# SDP21_Daughter_Board_Schematic.net
KiCad netlist of a schematic drawn in Altium Designer
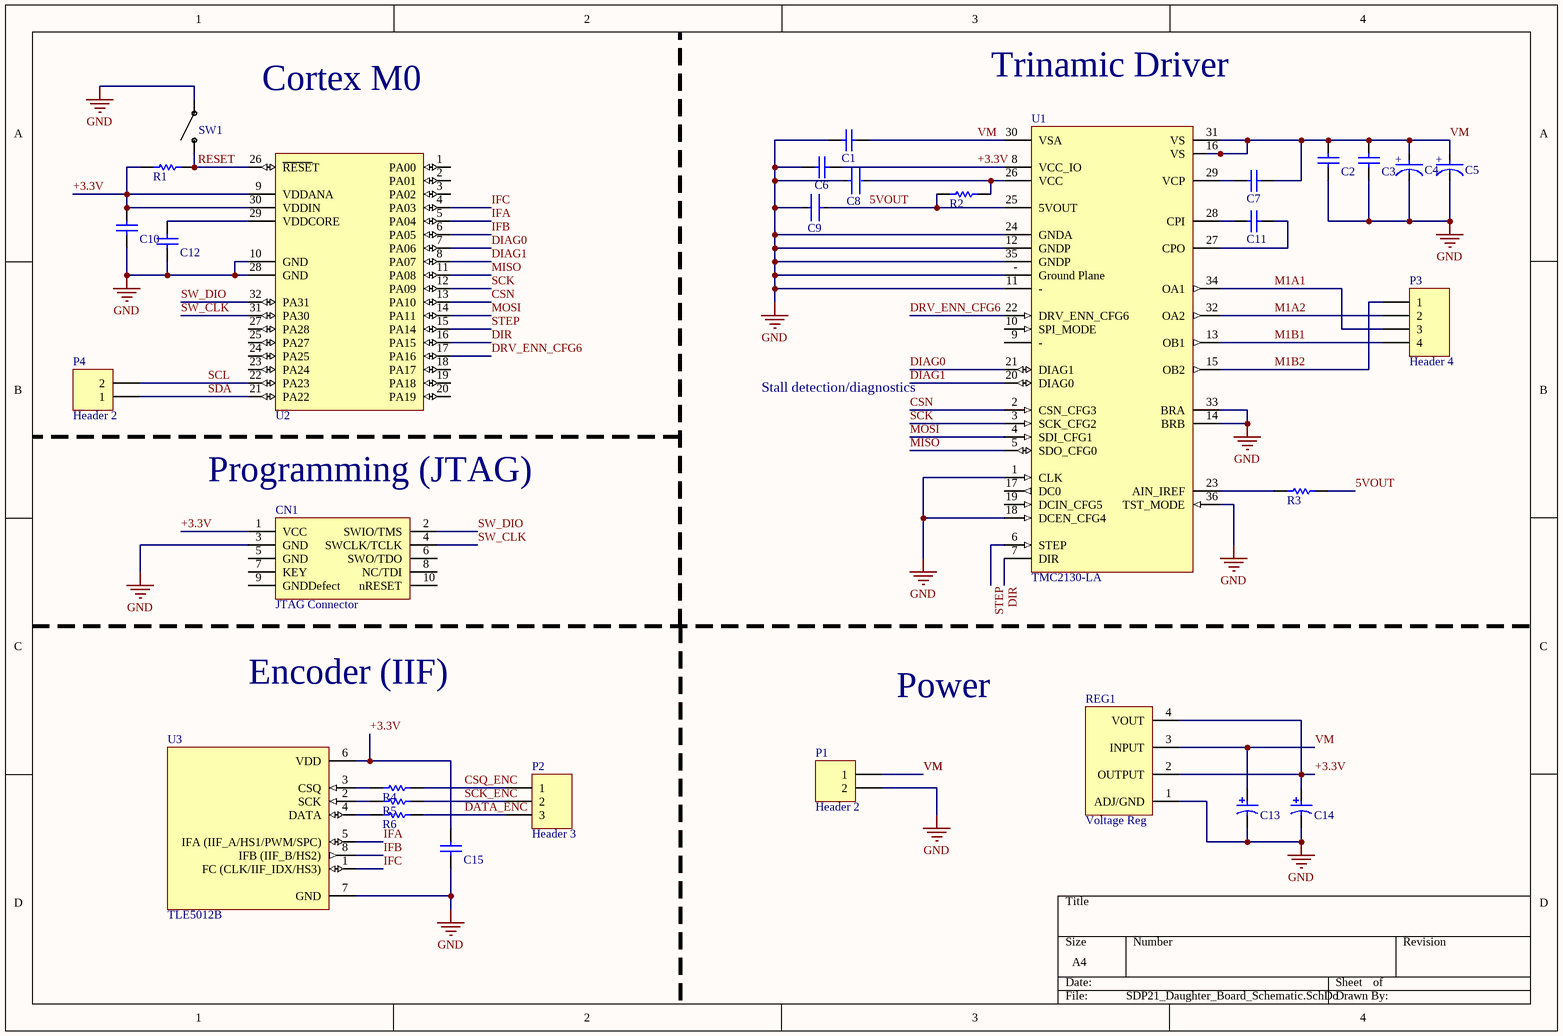
[diagram p0: SDP21_Daughter_Board_Schematic.SchDoc]

(export (version "E")
  (design (tool "Eeschema 10.0.6"))
  (components
    (comp (ref "C1")
      (value "CGA3E2X7R1H104K080AA")
      (footprint "CAPC1608X90X20LL10")
      (description "Chip Capacitor, 0.1 uF, +/- 10%, 50 V, -55 to 125 degC, 0603 (1608 Metric), RoHS, Tape and Reel")
      (fields (field (name "VOLTAGE") "50V") (field (name "TOLERANCE") "10%"))
      (libsource (lib "Altium Content Vault") (part "CAP-NP-2"))
    )
    (comp (ref "C2")
      (value "CGA3E2X7R1H104K080AA")
      (footprint "CAPC1608X90X20LL10")
      (description "Chip Capacitor, 0.1 uF, +/- 10%, 50 V, -55 to 125 degC, 0603 (1608 Metric), RoHS, Tape and Reel")
      (fields (field (name "VOLTAGE") "50V") (field (name "TOLERANCE") "10%"))
      (libsource (lib "Altium Content Vault") (part "CAP-NP-2"))
    )
    (comp (ref "C3")
      (value "C1210C476M4PACTU")
      (footprint "CAPC3225X270X50LL20T25")
      (description "Chip Capacitor, 47 uF, +/- 20%, 16 V, -55 to 85 degC, 1210 (3225 Metric), RoHS, Tape and Reel")
      (fields (field (name "TOLERANCE") "±20%") (field (name "MANUFACTURER") "Kemet"))
      (libsource (lib "Altium Content Vault") (part "CAP-NP-2"))
    )
    (comp (ref "C4")
      (value "EEE-FK1H101P")
      (footprint "FP-EEE-FK1H101P-MFG")
      (description "CAP ALUM 100UF 20% 50V SMD")
      (fields
        (field (name "TOLERANCE") "20%")
        (field (name "OCTOPART") "https://octopart.com/eeefk1h101p-panasonic-4642841")
      )
      (libsource (lib "Altium Content Vault") (part "cf48714ba7e38822c1575c7ec0b6d1f"))
    )
    (comp (ref "C5")
      (value "EEE-FK1H101P")
      (footprint "FP-EEE-FK1H101P-MFG")
      (description "CAP ALUM 100UF 20% 50V SMD")
      (fields
        (field (name "TOLERANCE") "20%")
        (field (name "OCTOPART") "https://octopart.com/eeefk1h101p-panasonic-4642841")
      )
      (libsource (lib "Altium Content Vault") (part "cf48714ba7e38822c1575c7ec0b6d1f"))
    )
    (comp (ref "C6")
      (value "CGA3E2X7R1H104K080AA")
      (footprint "CAPC1608X90X20LL10")
      (description "Chip Capacitor, 0.1 uF, +/- 10%, 50 V, -55 to 125 degC, 0603 (1608 Metric), RoHS, Tape and Reel")
      (fields (field (name "VOLTAGE") "50V") (field (name "TOLERANCE") "10%"))
      (libsource (lib "Altium Content Vault") (part "CAP-NP-2"))
    )
    (comp (ref "C7")
      (value "CGA3E2X7R1H104K080AA")
      (footprint "CAPC1608X90X20LL10")
      (description "Chip Capacitor, 0.1 uF, +/- 10%, 50 V, -55 to 125 degC, 0603 (1608 Metric), RoHS, Tape and Reel")
      (fields (field (name "VOLTAGE") "50V") (field (name "TOLERANCE") "10%"))
      (libsource (lib "Altium Content Vault") (part "CAP-NP-2"))
    )
    (comp (ref "C8")
      (value "C0603C474K4RACTU")
      (footprint "FP-C0603C-CF-MFG")
      (description "CAP CER 0.47UF 16V X7R 0603")
      (fields
        (field (name "TOLERANCE") "0.1")
        (field (name "OCTOPART") "https://octopart.com/c0603c474k4ractu-kemet-109683")
      )
      (libsource (lib "Altium Content Vault") (part "b4654b650e69147ec39a6b967a45e02"))
    )
    (comp (ref "C9")
      (value "C0603C475K9PACTU")
      (footprint "FP-C0603-CG-MFG")
      (description "CAP CER 4.7UF 6.3V X5R 0603")
      (fields (field (name "TOLERANCE") "10%") (field (name "MANUFACTURER") "Kemet"))
      (libsource (lib "Altium Content Vault") (part "11868f565c42a9108669ba33697ecf6"))
    )
    (comp (ref "C10")
      (value "GRM188R60J106ME47D")
      (footprint "CAPC1608X90X35NL10T15")
      (fields (field (name "MANUFACTURER") "Murata"))
      (libsource (lib "Altium Content Vault") (part "CAP"))
    )
    (comp (ref "C11")
      (value "CC0603KRX7R9BB223")
      (footprint "CAPC1608X90X40ML10T20")
      (description "Chip Capacitor, 22 nF, +/- 10%, 50 V, -55 to 125 degC, 0603 (1608 Metric), RoHS, Tape and Reel")
      (fields (field (name "MANUFACTURER") "Yageo") (field (name "TOLERANCE") "10%"))
      (libsource (lib "Altium Content Vault") (part "CAP-NP-2"))
    )
    (comp (ref "C12")
      (value "GRM188R60J106ME47D")
      (footprint "CAPC1608X90X35NL10T15")
      (fields (field (name "MANUFACTURER") "Murata"))
      (libsource (lib "Altium Content Vault") (part "CAP"))
    )
    (comp (ref "C13")
      (value "T491A106K010AT")
      (footprint "KEMT-A-3216-18-2_M")
      (description "Capacitor, Tantalum, 10 uF, +/- 10%, 10 V, -55 to 125 degC, 2-Pin SMD (1206), RoHS, Tape and Reel")
      (fields (field (name "TOLERANCE") "±10%") (field (name "MANUFACTURER") "Kemet"))
      (libsource (lib "Altium Content Vault") (part "CAP-P-2"))
    )
    (comp (ref "C14")
      (value "TAJA226K010RNJ")
      (footprint "AVX-TAJ-A-2_L")
      (description "Chip Capacitor, 22 uF, +/- 10%, 10 V, -55 to 125 degC, 1206 (3216 Metric), RoHS, Tape and Reel")
      (fields (field (name "MANUFACTURER") "AVX") (field (name "TOLERANCE") "10%"))
      (libsource (lib "Altium Content Vault") (part "CAP-P-2"))
    )
    (comp (ref "C15")
      (value "CGA3E2X7R1H104K080AA")
      (footprint "CAPC1608X90X20LL10")
      (description "Chip Capacitor, 0.1 uF, +/- 10%, 50 V, -55 to 125 degC, 0603 (1608 Metric), RoHS, Tape and Reel")
      (fields (field (name "VOLTAGE") "50V") (field (name "TOLERANCE") "10%"))
      (libsource (lib "Altium Content Vault") (part "CAP-NP-2"))
    )
    (comp (ref "CN1")
      (value "JTAG Connector")
      (footprint "Header 5x2 - 50mil")
      (libsource (lib "SDP21_Symbols") (part "JTAG Connector"))
    )
    (comp (ref "P1")
      (value "Header 2")
      (footprint "HDR1X2")
      (description "Header, 2-Pin")
      (fields (field (name "PUBLISHER") "Altium Limited"))
      (libsource (lib "Miscellaneous Connectors") (part "Header 2"))
    )
    (comp (ref "P2")
      (value "Header 3")
      (footprint "HDR1X3")
      (description "Header, 3-Pin")
      (fields (field (name "PUBLISHER") "Altium Limited"))
      (libsource (lib "Miscellaneous Connectors") (part "Header 3"))
    )
    (comp (ref "P3")
      (value "Header 4")
      (footprint "HDR1X4")
      (description "Header, 4-Pin")
      (fields (field (name "PUBLISHER") "Altium Limited"))
      (libsource (lib "Miscellaneous Connectors") (part "Header 4"))
    )
    (comp (ref "P4")
      (value "Header 2")
      (footprint "HDR1X2")
      (description "Header, 2-Pin")
      (fields (field (name "PUBLISHER") "Altium Limited"))
      (libsource (lib "") (part "Header 2_1"))
    )
    (comp (ref "R1")
      (value "ERJ3EKF1002V")
      (footprint "RESC1609X55X30LL15T15")
      (description "Chip Resistor, 10 KOhm, +/- 1%, 0.1 W, -55 to 155 degC, 0603 (1608 Metric), RoHS, Tape and Reel")
      (fields (field (name "TOLERANCE") "1%") (field (name "MANUFACTURER") "Panasonic"))
      (libsource (lib "Altium Content Vault") (part "RES-2"))
    )
    (comp (ref "R2")
      (value "CRCW06033R30JNEA")
      (footprint "RESC1609X50X30ML10T20")
      (fields (field (name "MANUFACTURER") "Vishay Dale"))
      (libsource (lib "Altium Content Vault") (part "RES"))
    )
    (comp (ref "R3")
      (value "ERJ3EKF1002V")
      (footprint "RESC1609X55X30LL15T15")
      (description "Chip Resistor, 10 KOhm, +/- 1%, 0.1 W, -55 to 155 degC, 0603 (1608 Metric), RoHS, Tape and Reel")
      (fields (field (name "TOLERANCE") "1%") (field (name "MANUFACTURER") "Panasonic"))
      (libsource (lib "Altium Content Vault") (part "RES-2"))
    )
    (comp (ref "R4")
      (value "470R 1% 0603(1608)")
      (footprint "RESC0603(1608)_M")
      (description "470R 0.1W 1% 0603 (1608 Metric)  SMD")
      (fields (field (name "POWER") "0.1 W") (field (name "TOLERANCE") "1 %"))
      (libsource (lib "Altium Content Vault") (part "RES"))
    )
    (comp (ref "R5")
      (value "470R 1% 0603(1608)")
      (footprint "RESC0603(1608)_M")
      (description "470R 0.1W 1% 0603 (1608 Metric)  SMD")
      (fields (field (name "POWER") "0.1 W") (field (name "TOLERANCE") "1 %"))
      (libsource (lib "Altium Content Vault") (part "RES"))
    )
    (comp (ref "R6")
      (value "470R 1% 0603(1608)")
      (footprint "RESC0603(1608)_M")
      (description "470R 0.1W 1% 0603 (1608 Metric)  SMD")
      (fields (field (name "POWER") "0.1 W") (field (name "TOLERANCE") "1 %"))
      (libsource (lib "Altium Content Vault") (part "RES"))
    )
    (comp (ref "REG1")
      (value "Voltage Reg")
      (footprint "SOT223")
      (libsource (lib "SDP21_Symbols") (part "Voltage Reg"))
    )
    (comp (ref "SW1")
      (value "PTS525SM15SMTR2 LFS")
      (footprint "PTS525 SM08 SMTR2 LFS")
      (description "SWITCH TACTILE SPST-NO 0.02A 15V")
      (libsource (lib "SDP21_Symbols") (part "Tactile Push Button"))
    )
    (comp (ref "U1")
      (value "TMC2130-LA")
      (footprint "QFN-36")
      (description "TMC2130-LA Trinamic Driver QFN-36")
      (libsource (lib "SDP21_Symbols") (part "TMC2130-LA"))
    )
    (comp (ref "U2")
      (value "ATSAMD21E15B-AUT")
      (footprint "TQFP-32")
      (description "IC MCU 32BIT 32KB FLASH 32TQFP")
      (libsource (lib "SDP21_Symbols") (part "ATSAMD21E15B-AUT"))
    )
    (comp (ref "U3")
      (value "TLE5012B")
      (footprint "PG-DSO-8")
      (description "TLE5012B GMR-Based Angle Sensor PG-DSO-8")
      (libsource (lib "SDP21_Symbols") (part "TLE5012B"))
    )
  )
  (nets
    (net (code "1") (name "/+3.3V") (class "Default")
      (node (ref "C10") (pin "2") (pinfunction "2_2") (pintype "passive"))
      (node (ref "C14") (pin "1") (pinfunction "1_1") (pintype "passive"))
      (node (ref "C15") (pin "2") (pinfunction "2_2") (pintype "passive"))
      (node (ref "C6") (pin "2") (pinfunction "2_2") (pintype "passive"))
      (node (ref "CN1") (pin "1") (pinfunction "VCC_1") (pintype "power_in"))
      (node (ref "R1") (pin "1") (pinfunction "1_1") (pintype "passive"))
      (node (ref "REG1") (pin "2") (pinfunction "OUTPUT_2") (pintype "passive"))
      (node (ref "REG1") (pin "4") (pinfunction "VOUT_4") (pintype "passive"))
      (node (ref "U1") (pin "8") (pinfunction "VCC_IO_8") (pintype "power_in"))
      (node (ref "U2") (pin "30") (pinfunction "VDDIN_30") (pintype "power_in"))
      (node (ref "U2") (pin "9") (pinfunction "VDDANA_9") (pintype "power_in"))
      (node (ref "U3") (pin "6") (pinfunction "VDD_6") (pintype "power_in"))
    )
    (net (code "2") (name "/5VOUT") (class "Default")
      (node (ref "C9") (pin "1") (pinfunction "1_1") (pintype "passive"))
      (node (ref "R2") (pin "1") (pinfunction "1_1") (pintype "passive"))
      (node (ref "R3") (pin "2") (pinfunction "2_2") (pintype "passive"))
      (node (ref "U1") (pin "25") (pinfunction "5VOUT_25") (pintype "power_in"))
    )
    (net (code "3") (name "/CSN") (class "Default")
      (node (ref "U1") (pin "2") (pinfunction "CSN_CFG3_2") (pintype "input"))
      (node (ref "U2") (pin "13") (pinfunction "PA10_13") (pintype "bidirectional"))
    )
    (net (code "4") (name "/CSQ_ENC") (class "Default")
      (node (ref "P2") (pin "1") (pinfunction "1_1") (pintype "passive"))
      (node (ref "R4") (pin "2") (pinfunction "2_2") (pintype "passive"))
    )
    (net (code "5") (name "/DATA_ENC") (class "Default")
      (node (ref "P2") (pin "3") (pinfunction "3_3") (pintype "passive"))
      (node (ref "R6") (pin "2") (pinfunction "2_2") (pintype "passive"))
    )
    (net (code "6") (name "/DIAG0") (class "Default")
      (node (ref "U1") (pin "21") (pinfunction "DIAG1_21") (pintype "bidirectional"))
      (node (ref "U2") (pin "7") (pinfunction "PA06_7") (pintype "bidirectional"))
    )
    (net (code "7") (name "/DIAG1") (class "Default")
      (node (ref "U1") (pin "20") (pinfunction "DIAG0_20") (pintype "bidirectional"))
      (node (ref "U2") (pin "8") (pinfunction "PA07_8") (pintype "bidirectional"))
    )
    (net (code "8") (name "/DIR") (class "Default")
      (node (ref "U1") (pin "7") (pinfunction "DIR_7") (pintype "passive"))
      (node (ref "U2") (pin "16") (pinfunction "PA15_16") (pintype "bidirectional"))
    )
    (net (code "9") (name "/DRV_ENN_CFG6") (class "Default")
      (node (ref "U1") (pin "22") (pinfunction "DRV_ENN_CFG6_22") (pintype "input"))
      (node (ref "U2") (pin "17") (pinfunction "PA16_17") (pintype "bidirectional"))
    )
    (net (code "10") (name "/IFA") (class "Default")
      (node (ref "U2") (pin "5") (pinfunction "PA04_5") (pintype "bidirectional"))
      (node (ref "U3") (pin "5") (pinfunction "IFA_(IIF_A/HS1/PWM/SPC)_5") (pintype "bidirectional"))
    )
    (net (code "11") (name "/IFB") (class "Default")
      (node (ref "U2") (pin "6") (pinfunction "PA05_6") (pintype "bidirectional"))
      (node (ref "U3") (pin "8") (pinfunction "IFB_(IIF_B/HS2)_8") (pintype "output"))
    )
    (net (code "12") (name "/IFC") (class "Default")
      (node (ref "U2") (pin "4") (pinfunction "PA03_4") (pintype "bidirectional"))
      (node (ref "U3") (pin "1") (pinfunction "FC_(CLK/IIF_IDX/HS3)_1") (pintype "bidirectional"))
    )
    (net (code "13") (name "/M1A1") (class "Default")
      (node (ref "P3") (pin "3") (pinfunction "3_3") (pintype "passive"))
      (node (ref "U1") (pin "34") (pinfunction "OA1_34") (pintype "output"))
    )
    (net (code "14") (name "/M1A2") (class "Default")
      (node (ref "P3") (pin "2") (pinfunction "2_2") (pintype "passive"))
      (node (ref "U1") (pin "32") (pinfunction "OA2_32") (pintype "output"))
    )
    (net (code "15") (name "/M1B1") (class "Default")
      (node (ref "P3") (pin "4") (pinfunction "4_4") (pintype "passive"))
      (node (ref "U1") (pin "13") (pinfunction "OB1_13") (pintype "output"))
    )
    (net (code "16") (name "/M1B2") (class "Default")
      (node (ref "P3") (pin "1") (pinfunction "1_1") (pintype "passive"))
      (node (ref "U1") (pin "15") (pinfunction "OB2_15") (pintype "output"))
    )
    (net (code "17") (name "/MISO") (class "Default")
      (node (ref "U1") (pin "5") (pinfunction "SDO_CFG0_5") (pintype "bidirectional"))
      (node (ref "U2") (pin "11") (pinfunction "PA08_11") (pintype "bidirectional"))
    )
    (net (code "18") (name "/MOSI") (class "Default")
      (node (ref "U1") (pin "4") (pinfunction "SDI_CFG1_4") (pintype "input"))
      (node (ref "U2") (pin "14") (pinfunction "PA11_14") (pintype "bidirectional"))
    )
    (net (code "19") (name "/RESET") (class "Default")
      (node (ref "R1") (pin "2") (pinfunction "2_2") (pintype "passive"))
      (node (ref "SW1") (pin "1") (pinfunction "1_1") (pintype "passive"))
      (node (ref "U2") (pin "26") (pinfunction "~{RESE}T_26") (pintype "bidirectional"))
    )
    (net (code "20") (name "/SCK") (class "Default")
      (node (ref "U1") (pin "3") (pinfunction "SCK_CFG2_3") (pintype "input"))
      (node (ref "U2") (pin "12") (pinfunction "PA09_12") (pintype "bidirectional"))
    )
    (net (code "21") (name "/SCK_ENC") (class "Default")
      (node (ref "P2") (pin "2") (pinfunction "2_2") (pintype "passive"))
      (node (ref "R5") (pin "2") (pinfunction "2_2") (pintype "passive"))
    )
    (net (code "22") (name "/SCL") (class "Default")
      (node (ref "P4") (pin "2") (pinfunction "2_2") (pintype "passive"))
      (node (ref "U2") (pin "22") (pinfunction "PA23_22") (pintype "bidirectional"))
    )
    (net (code "23") (name "/SDA") (class "Default")
      (node (ref "P4") (pin "1") (pinfunction "1_1") (pintype "passive"))
      (node (ref "U2") (pin "21") (pinfunction "PA22_21") (pintype "bidirectional"))
    )
    (net (code "24") (name "/STEP") (class "Default")
      (node (ref "U1") (pin "6") (pinfunction "STEP_6") (pintype "input"))
      (node (ref "U2") (pin "15") (pinfunction "PA14_15") (pintype "bidirectional"))
    )
    (net (code "25") (name "/SW_CLK") (class "Default")
      (node (ref "CN1") (pin "4") (pinfunction "SWCLK/TCLK_4") (pintype "power_in"))
      (node (ref "U2") (pin "31") (pinfunction "PA30_31") (pintype "bidirectional"))
    )
    (net (code "26") (name "/SW_DIO") (class "Default")
      (node (ref "CN1") (pin "2") (pinfunction "SWIO/TMS_2") (pintype "power_in"))
      (node (ref "U2") (pin "32") (pinfunction "PA31_32") (pintype "bidirectional"))
    )
    (net (code "27") (name "/VM") (class "Default")
      (node (ref "C1") (pin "2") (pinfunction "2_2") (pintype "passive"))
      (node (ref "C13") (pin "1") (pinfunction "1_1") (pintype "passive"))
      (node (ref "C2") (pin "2") (pinfunction "2_2") (pintype "passive"))
      (node (ref "C3") (pin "2") (pinfunction "2_2") (pintype "passive"))
      (node (ref "C4") (pin "2") (pinfunction "A_2") (pintype "passive"))
      (node (ref "C5") (pin "2") (pinfunction "A_2") (pintype "passive"))
      (node (ref "C7") (pin "1") (pinfunction "1_1") (pintype "passive"))
      (node (ref "P1") (pin "1") (pinfunction "1_1") (pintype "passive"))
      (node (ref "REG1") (pin "3") (pinfunction "INPUT_3") (pintype "passive"))
      (node (ref "U1") (pin "16") (pinfunction "VS_16") (pintype "power_in"))
      (node (ref "U1") (pin "30") (pinfunction "VSA_30") (pintype "power_in"))
      (node (ref "U1") (pin "31") (pinfunction "VS_31") (pintype "power_in"))
    )
    (net (code "28") (name "GND") (class "Default")
      (node (ref "C1") (pin "1") (pinfunction "1_1") (pintype "passive"))
      (node (ref "C10") (pin "1") (pinfunction "1_1") (pintype "passive"))
      (node (ref "C12") (pin "1") (pinfunction "1_1") (pintype "passive"))
      (node (ref "C13") (pin "2") (pinfunction "2_2") (pintype "passive"))
      (node (ref "C14") (pin "2") (pinfunction "2_2") (pintype "passive"))
      (node (ref "C15") (pin "1") (pinfunction "1_1") (pintype "passive"))
      (node (ref "C2") (pin "1") (pinfunction "1_1") (pintype "passive"))
      (node (ref "C3") (pin "1") (pinfunction "1_1") (pintype "passive"))
      (node (ref "C4") (pin "1") (pinfunction "C_1") (pintype "passive"))
      (node (ref "C5") (pin "1") (pinfunction "C_1") (pintype "passive"))
      (node (ref "C6") (pin "1") (pinfunction "1_1") (pintype "passive"))
      (node (ref "C8") (pin "1") (pinfunction "1_1") (pintype "passive"))
      (node (ref "C9") (pin "2") (pinfunction "2_2") (pintype "passive"))
      (node (ref "CN1") (pin "3") (pinfunction "GND_3") (pintype "power_in"))
      (node (ref "P1") (pin "2") (pinfunction "2_2") (pintype "passive"))
      (node (ref "REG1") (pin "1") (pinfunction "ADJ/GND_1") (pintype "passive"))
      (node (ref "SW1") (pin "2") (pinfunction "2_2") (pintype "passive"))
      (node (ref "U1") (pin "-") (pinfunction "Ground_Plane_-") (pintype "passive"))
      (node (ref "U1") (pin "1") (pinfunction "CLK_1") (pintype "input"))
      (node (ref "U1") (pin "11") (pinfunction "-_11") (pintype "passive"))
      (node (ref "U1") (pin "12") (pinfunction "GNDP_12") (pintype "power_in"))
      (node (ref "U1") (pin "14") (pinfunction "BRB_14") (pintype "passive"))
      (node (ref "U1") (pin "18") (pinfunction "DCEN_CFG4_18") (pintype "input"))
      (node (ref "U1") (pin "24") (pinfunction "GNDA_24") (pintype "power_in"))
      (node (ref "U1") (pin "33") (pinfunction "BRA_33") (pintype "passive"))
      (node (ref "U1") (pin "35") (pinfunction "GNDP_35") (pintype "power_in"))
      (node (ref "U1") (pin "36") (pinfunction "TST_MODE_36") (pintype "input"))
      (node (ref "U2") (pin "10") (pinfunction "GND_10") (pintype "power_in"))
      (node (ref "U2") (pin "28") (pinfunction "GND_28") (pintype "power_in"))
      (node (ref "U3") (pin "7") (pinfunction "GND_7") (pintype "power_in"))
    )
    (net (code "29") (name "Net-(U1-AIN_IREF)") (class "Default")
      (node (ref "R3") (pin "1") (pinfunction "1_1") (pintype "passive"))
      (node (ref "U1") (pin "23") (pinfunction "AIN_IREF_23") (pintype "passive"))
    )
    (net (code "30") (name "Net-(U1-CPI)") (class "Default")
      (node (ref "C11") (pin "1") (pinfunction "1_1") (pintype "passive"))
      (node (ref "U1") (pin "28") (pinfunction "CPI_28") (pintype "passive"))
    )
    (net (code "31") (name "Net-(U1-CPO)") (class "Default")
      (node (ref "C11") (pin "2") (pinfunction "2_2") (pintype "passive"))
      (node (ref "U1") (pin "27") (pinfunction "CPO_27") (pintype "passive"))
    )
    (net (code "32") (name "Net-(U1-VCC)") (class "Default")
      (node (ref "C8") (pin "2") (pinfunction "2_2") (pintype "passive"))
      (node (ref "R2") (pin "2") (pinfunction "2_2") (pintype "passive"))
      (node (ref "U1") (pin "26") (pinfunction "VCC_26") (pintype "power_in"))
    )
    (net (code "33") (name "Net-(U1-VCP)") (class "Default")
      (node (ref "C7") (pin "2") (pinfunction "2_2") (pintype "passive"))
      (node (ref "U1") (pin "29") (pinfunction "VCP_29") (pintype "passive"))
    )
    (net (code "34") (name "Net-(U2-VDDCORE)") (class "Default")
      (node (ref "C12") (pin "2") (pinfunction "2_2") (pintype "passive"))
      (node (ref "U2") (pin "29") (pinfunction "VDDCORE_29") (pintype "power_in"))
    )
    (net (code "35") (name "Net-(U3-CSQ)") (class "Default")
      (node (ref "R4") (pin "1") (pinfunction "1_1") (pintype "passive"))
      (node (ref "U3") (pin "3") (pinfunction "CSQ_3") (pintype "input"))
    )
    (net (code "36") (name "Net-(U3-DATA)") (class "Default")
      (node (ref "R6") (pin "1") (pinfunction "1_1") (pintype "passive"))
      (node (ref "U3") (pin "4") (pinfunction "DATA_4") (pintype "bidirectional"))
    )
    (net (code "37") (name "Net-(U3-SCK)") (class "Default")
      (node (ref "R5") (pin "1") (pinfunction "1_1") (pintype "passive"))
      (node (ref "U3") (pin "2") (pinfunction "SCK_2") (pintype "input"))
    )
    (net (code "38") (name "unconnected-(CN1-GND-Pad5)") (class "Default")
      (node (ref "CN1") (pin "5") (pinfunction "GND_5") (pintype "power_in"))
    )
    (net (code "39") (name "unconnected-(CN1-GNDDefect-Pad9)") (class "Default")
      (node (ref "CN1") (pin "9") (pinfunction "GNDDefect_9") (pintype "power_in"))
    )
    (net (code "40") (name "unconnected-(CN1-KEY-Pad7)") (class "Default")
      (node (ref "CN1") (pin "7") (pinfunction "KEY_7") (pintype "power_in"))
    )
    (net (code "41") (name "unconnected-(CN1-NC{slash}TDI-Pad8)") (class "Default")
      (node (ref "CN1") (pin "8") (pinfunction "NC/TDI_8") (pintype "power_in"))
    )
    (net (code "42") (name "unconnected-(CN1-SWO{slash}TDO-Pad6)") (class "Default")
      (node (ref "CN1") (pin "6") (pinfunction "SWO/TDO_6") (pintype "power_in"))
    )
    (net (code "43") (name "unconnected-(CN1-nRESET-Pad10)") (class "Default")
      (node (ref "CN1") (pin "10") (pinfunction "nRESET_10") (pintype "power_in"))
    )
    (net (code "44") (name "unconnected-(U1---Pad9)") (class "Default")
      (node (ref "U1") (pin "9") (pinfunction "-_9") (pintype "tri_state"))
    )
    (net (code "45") (name "unconnected-(U1-DC0-Pad17)") (class "Default")
      (node (ref "U1") (pin "17") (pinfunction "DC0_17") (pintype "output"))
    )
    (net (code "46") (name "unconnected-(U1-DCIN_CFG5-Pad19)") (class "Default")
      (node (ref "U1") (pin "19") (pinfunction "DCIN_CFG5_19") (pintype "input"))
    )
    (net (code "47") (name "unconnected-(U1-SPI_MODE-Pad10)") (class "Default")
      (node (ref "U1") (pin "10") (pinfunction "SPI_MODE_10") (pintype "input"))
    )
    (net (code "48") (name "unconnected-(U2-PA00-Pad1)") (class "Default")
      (node (ref "U2") (pin "1") (pinfunction "PA00_1") (pintype "bidirectional"))
    )
    (net (code "49") (name "unconnected-(U2-PA01-Pad2)") (class "Default")
      (node (ref "U2") (pin "2") (pinfunction "PA01_2") (pintype "bidirectional"))
    )
    (net (code "50") (name "unconnected-(U2-PA02-Pad3)") (class "Default")
      (node (ref "U2") (pin "3") (pinfunction "PA02_3") (pintype "bidirectional"))
    )
    (net (code "51") (name "unconnected-(U2-PA17-Pad18)") (class "Default")
      (node (ref "U2") (pin "18") (pinfunction "PA17_18") (pintype "bidirectional"))
    )
    (net (code "52") (name "unconnected-(U2-PA18-Pad19)") (class "Default")
      (node (ref "U2") (pin "19") (pinfunction "PA18_19") (pintype "bidirectional"))
    )
    (net (code "53") (name "unconnected-(U2-PA19-Pad20)") (class "Default")
      (node (ref "U2") (pin "20") (pinfunction "PA19_20") (pintype "bidirectional"))
    )
    (net (code "54") (name "unconnected-(U2-PA24-Pad23)") (class "Default")
      (node (ref "U2") (pin "23") (pinfunction "PA24_23") (pintype "bidirectional"))
    )
    (net (code "55") (name "unconnected-(U2-PA25-Pad24)") (class "Default")
      (node (ref "U2") (pin "24") (pinfunction "PA25_24") (pintype "bidirectional"))
    )
    (net (code "56") (name "unconnected-(U2-PA27-Pad25)") (class "Default")
      (node (ref "U2") (pin "25") (pinfunction "PA27_25") (pintype "bidirectional"))
    )
    (net (code "57") (name "unconnected-(U2-PA28-Pad27)") (class "Default")
      (node (ref "U2") (pin "27") (pinfunction "PA28_27") (pintype "bidirectional"))
    )
  )
)
